# Shield_schematic.net
KiCad netlist of a schematic drawn in EAGLE
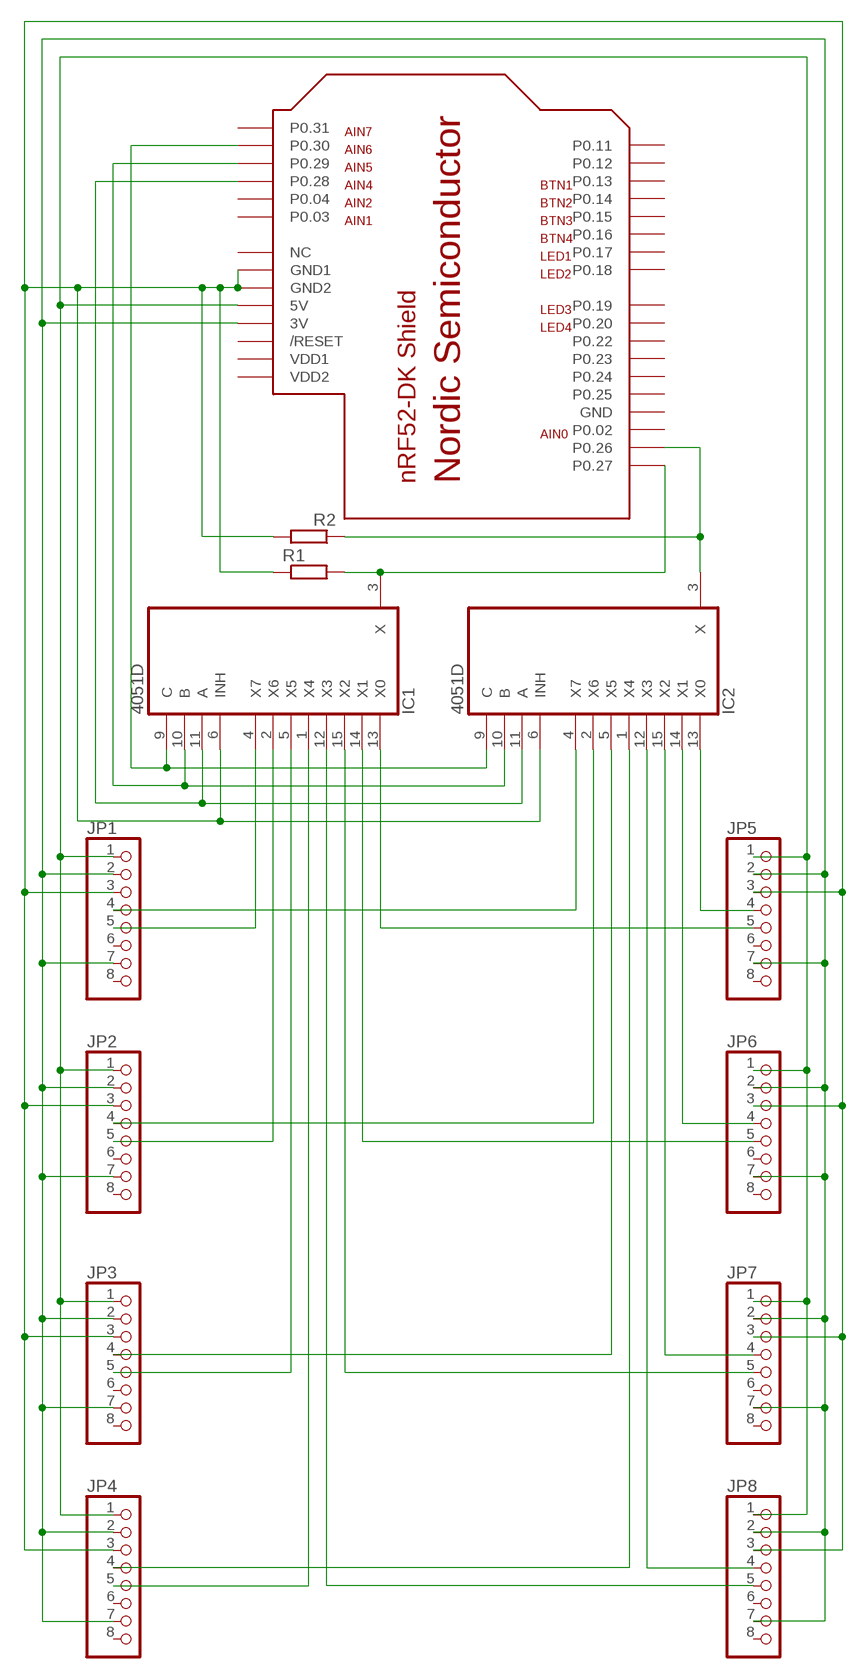
[diagram p0: schematic, sheet 1]

(export (version "E")
  (design (tool "Eeschema 10.0.6"))
  (components
    (comp (ref "IC1")
      (value "4051D")
      (footprint "eagle-import:SO16")
      (libsource (lib "eagle-import") (part "4051D"))
    )
    (comp (ref "IC2")
      (value "4051D")
      (footprint "eagle-import:SO16")
      (libsource (lib "eagle-import") (part "4051D"))
    )
    (comp (ref "JP1")
      (value "PINHD-1X8")
      (footprint "eagle-import:1X08")
      (libsource (lib "eagle-import") (part "PINHD-1X8"))
    )
    (comp (ref "JP2")
      (value "PINHD-1X8")
      (footprint "eagle-import:1X08")
      (libsource (lib "eagle-import") (part "PINHD-1X8"))
    )
    (comp (ref "JP3")
      (value "PINHD-1X8")
      (footprint "eagle-import:1X08")
      (libsource (lib "eagle-import") (part "PINHD-1X8"))
    )
    (comp (ref "JP4")
      (value "PINHD-1X8")
      (footprint "eagle-import:1X08")
      (libsource (lib "eagle-import") (part "PINHD-1X8"))
    )
    (comp (ref "JP5")
      (value "PINHD-1X8")
      (footprint "eagle-import:1X08")
      (libsource (lib "eagle-import") (part "PINHD-1X8"))
    )
    (comp (ref "JP6")
      (value "PINHD-1X8")
      (footprint "eagle-import:1X08")
      (libsource (lib "eagle-import") (part "PINHD-1X8"))
    )
    (comp (ref "JP7")
      (value "PINHD-1X8")
      (footprint "eagle-import:1X08")
      (libsource (lib "eagle-import") (part "PINHD-1X8"))
    )
    (comp (ref "JP8")
      (value "PINHD-1X8")
      (footprint "eagle-import:1X08")
      (libsource (lib "eagle-import") (part "PINHD-1X8"))
    )
    (comp (ref "R1")
      (value "R-EU_0411/15")
      (footprint "eagle-import:0411_15")
      (libsource (lib "eagle-import") (part "R-EU_0411/15"))
    )
    (comp (ref "R2")
      (value "R-EU_0411/15")
      (footprint "eagle-import:0411_15")
      (libsource (lib "eagle-import") (part "R-EU_0411/15"))
    )
    (comp (ref "U$1")
      (value "NRF52-SHIELD-NOTEXT")
      (footprint "eagle-import:NRF52-SHIELD")
      (libsource (lib "eagle-import") (part "NRF52-SHIELD-NOTEXT"))
    )
  )
  (nets
    (net (code "1") (name "/GND") (class "Default")
      (node (ref "U$1") (pin "GND") (pinfunction "GND_GND") (pintype "power_in"))
    )
    (net (code "2") (name "/VDD1") (class "Default")
      (node (ref "U$1") (pin "VDD2") (pinfunction "VDD1_VDD2") (pintype "power_in"))
    )
    (net (code "3") (name "/VDD2") (class "Default")
      (node (ref "U$1") (pin "VDD1") (pinfunction "VDD2_VDD1") (pintype "power_in"))
    )
    (net (code "4") (name "Net-(IC1A-A)") (class "Default")
      (node (ref "IC1") (pin "11") (pinfunction "A_11") (pintype "input"))
      (node (ref "IC2") (pin "11") (pinfunction "A_11") (pintype "input"))
      (node (ref "U$1") (pin "P28") (pinfunction "P0.28_P28") (pintype "bidirectional"))
    )
    (net (code "5") (name "Net-(IC1A-B)") (class "Default")
      (node (ref "IC1") (pin "10") (pinfunction "B_10") (pintype "input"))
      (node (ref "IC2") (pin "10") (pinfunction "B_10") (pintype "input"))
      (node (ref "U$1") (pin "P29") (pinfunction "P0.29_P29") (pintype "bidirectional"))
    )
    (net (code "6") (name "Net-(IC1A-C)") (class "Default")
      (node (ref "IC1") (pin "9") (pinfunction "C_9") (pintype "input"))
      (node (ref "IC2") (pin "9") (pinfunction "C_9") (pintype "input"))
      (node (ref "U$1") (pin "P30") (pinfunction "P0.30_P30") (pintype "bidirectional"))
    )
    (net (code "7") (name "Net-(IC1A-INH)") (class "Default")
      (node (ref "IC1") (pin "6") (pinfunction "INH_6") (pintype "input"))
      (node (ref "IC2") (pin "6") (pinfunction "INH_6") (pintype "input"))
      (node (ref "JP1") (pin "3") (pinfunction "3_3") (pintype "passive"))
      (node (ref "JP2") (pin "3") (pinfunction "3_3") (pintype "passive"))
      (node (ref "JP3") (pin "3") (pinfunction "3_3") (pintype "passive"))
      (node (ref "JP4") (pin "3") (pinfunction "3_3") (pintype "passive"))
      (node (ref "JP5") (pin "3") (pinfunction "3_3") (pintype "passive"))
      (node (ref "JP6") (pin "3") (pinfunction "3_3") (pintype "passive"))
      (node (ref "JP7") (pin "3") (pinfunction "3_3") (pintype "passive"))
      (node (ref "JP8") (pin "3") (pinfunction "3_3") (pintype "passive"))
      (node (ref "R1") (pin "1") (pinfunction "1_1") (pintype "passive"))
      (node (ref "R2") (pin "2") (pinfunction "2_2") (pintype "passive"))
      (node (ref "U$1") (pin "GND1") (pinfunction "GND1_GND1") (pintype "power_in"))
      (node (ref "U$1") (pin "GND2") (pinfunction "GND2_GND2") (pintype "power_in"))
    )
    (net (code "8") (name "Net-(IC1A-X)") (class "Default")
      (node (ref "IC1") (pin "3") (pinfunction "X_3") (pintype "bidirectional"))
      (node (ref "R1") (pin "2") (pinfunction "2_2") (pintype "passive"))
      (node (ref "U$1") (pin "P27") (pinfunction "P0.27_P27") (pintype "bidirectional"))
    )
    (net (code "9") (name "Net-(IC1A-X0)") (class "Default")
      (node (ref "IC1") (pin "13") (pinfunction "X0_13") (pintype "bidirectional"))
      (node (ref "JP5") (pin "5") (pinfunction "5_5") (pintype "passive"))
    )
    (net (code "10") (name "Net-(IC1A-X1)") (class "Default")
      (node (ref "IC1") (pin "14") (pinfunction "X1_14") (pintype "bidirectional"))
      (node (ref "JP6") (pin "5") (pinfunction "5_5") (pintype "passive"))
    )
    (net (code "11") (name "Net-(IC1A-X2)") (class "Default")
      (node (ref "IC1") (pin "15") (pinfunction "X2_15") (pintype "bidirectional"))
      (node (ref "JP7") (pin "5") (pinfunction "5_5") (pintype "passive"))
    )
    (net (code "12") (name "Net-(IC1A-X3)") (class "Default")
      (node (ref "IC1") (pin "12") (pinfunction "X3_12") (pintype "bidirectional"))
      (node (ref "JP8") (pin "5") (pinfunction "5_5") (pintype "passive"))
    )
    (net (code "13") (name "Net-(IC1A-X4)") (class "Default")
      (node (ref "IC1") (pin "1") (pinfunction "X4_1") (pintype "bidirectional"))
      (node (ref "JP4") (pin "5") (pinfunction "5_5") (pintype "passive"))
    )
    (net (code "14") (name "Net-(IC1A-X5)") (class "Default")
      (node (ref "IC1") (pin "5") (pinfunction "X5_5") (pintype "bidirectional"))
      (node (ref "JP3") (pin "5") (pinfunction "5_5") (pintype "passive"))
    )
    (net (code "15") (name "Net-(IC1A-X6)") (class "Default")
      (node (ref "IC1") (pin "2") (pinfunction "X6_2") (pintype "bidirectional"))
      (node (ref "JP2") (pin "5") (pinfunction "5_5") (pintype "passive"))
    )
    (net (code "16") (name "Net-(IC1A-X7)") (class "Default")
      (node (ref "IC1") (pin "4") (pinfunction "X7_4") (pintype "bidirectional"))
      (node (ref "JP1") (pin "5") (pinfunction "5_5") (pintype "passive"))
    )
    (net (code "17") (name "Net-(IC2A-X)") (class "Default")
      (node (ref "IC2") (pin "3") (pinfunction "X_3") (pintype "bidirectional"))
      (node (ref "R2") (pin "1") (pinfunction "1_1") (pintype "passive"))
      (node (ref "U$1") (pin "P26") (pinfunction "P0.26_P26") (pintype "bidirectional"))
    )
    (net (code "18") (name "Net-(IC2A-X0)") (class "Default")
      (node (ref "IC2") (pin "13") (pinfunction "X0_13") (pintype "bidirectional"))
      (node (ref "JP5") (pin "4") (pinfunction "4_4") (pintype "passive"))
    )
    (net (code "19") (name "Net-(IC2A-X1)") (class "Default")
      (node (ref "IC2") (pin "14") (pinfunction "X1_14") (pintype "bidirectional"))
      (node (ref "JP6") (pin "4") (pinfunction "4_4") (pintype "passive"))
    )
    (net (code "20") (name "Net-(IC2A-X2)") (class "Default")
      (node (ref "IC2") (pin "15") (pinfunction "X2_15") (pintype "bidirectional"))
      (node (ref "JP7") (pin "4") (pinfunction "4_4") (pintype "passive"))
    )
    (net (code "21") (name "Net-(IC2A-X3)") (class "Default")
      (node (ref "IC2") (pin "12") (pinfunction "X3_12") (pintype "bidirectional"))
      (node (ref "JP8") (pin "4") (pinfunction "4_4") (pintype "passive"))
    )
    (net (code "22") (name "Net-(IC2A-X4)") (class "Default")
      (node (ref "IC2") (pin "1") (pinfunction "X4_1") (pintype "bidirectional"))
      (node (ref "JP4") (pin "4") (pinfunction "4_4") (pintype "passive"))
    )
    (net (code "23") (name "Net-(IC2A-X5)") (class "Default")
      (node (ref "IC2") (pin "5") (pinfunction "X5_5") (pintype "bidirectional"))
      (node (ref "JP3") (pin "4") (pinfunction "4_4") (pintype "passive"))
    )
    (net (code "24") (name "Net-(IC2A-X6)") (class "Default")
      (node (ref "IC2") (pin "2") (pinfunction "X6_2") (pintype "bidirectional"))
      (node (ref "JP2") (pin "4") (pinfunction "4_4") (pintype "passive"))
    )
    (net (code "25") (name "Net-(IC2A-X7)") (class "Default")
      (node (ref "IC2") (pin "4") (pinfunction "X7_4") (pintype "bidirectional"))
      (node (ref "JP1") (pin "4") (pinfunction "4_4") (pintype "passive"))
    )
    (net (code "26") (name "Net-(JP1-Pad1)") (class "Default")
      (node (ref "JP1") (pin "1") (pinfunction "1_1") (pintype "passive"))
      (node (ref "JP2") (pin "1") (pinfunction "1_1") (pintype "passive"))
      (node (ref "JP3") (pin "1") (pinfunction "1_1") (pintype "passive"))
      (node (ref "JP4") (pin "1") (pinfunction "1_1") (pintype "passive"))
      (node (ref "JP5") (pin "1") (pinfunction "1_1") (pintype "passive"))
      (node (ref "JP6") (pin "1") (pinfunction "1_1") (pintype "passive"))
      (node (ref "JP7") (pin "1") (pinfunction "1_1") (pintype "passive"))
      (node (ref "JP8") (pin "1") (pinfunction "1_1") (pintype "passive"))
      (node (ref "U$1") (pin "5V") (pinfunction "5V_5V") (pintype "power_in"))
    )
    (net (code "27") (name "Net-(JP1-Pad2)") (class "Default")
      (node (ref "JP1") (pin "2") (pinfunction "2_2") (pintype "passive"))
      (node (ref "JP1") (pin "7") (pinfunction "7_7") (pintype "passive"))
      (node (ref "JP2") (pin "2") (pinfunction "2_2") (pintype "passive"))
      (node (ref "JP2") (pin "7") (pinfunction "7_7") (pintype "passive"))
      (node (ref "JP3") (pin "2") (pinfunction "2_2") (pintype "passive"))
      (node (ref "JP3") (pin "7") (pinfunction "7_7") (pintype "passive"))
      (node (ref "JP4") (pin "2") (pinfunction "2_2") (pintype "passive"))
      (node (ref "JP4") (pin "7") (pinfunction "7_7") (pintype "passive"))
      (node (ref "JP5") (pin "2") (pinfunction "2_2") (pintype "passive"))
      (node (ref "JP5") (pin "7") (pinfunction "7_7") (pintype "passive"))
      (node (ref "JP6") (pin "2") (pinfunction "2_2") (pintype "passive"))
      (node (ref "JP6") (pin "7") (pinfunction "7_7") (pintype "passive"))
      (node (ref "JP7") (pin "2") (pinfunction "2_2") (pintype "passive"))
      (node (ref "JP7") (pin "7") (pinfunction "7_7") (pintype "passive"))
      (node (ref "JP8") (pin "2") (pinfunction "2_2") (pintype "passive"))
      (node (ref "JP8") (pin "7") (pinfunction "7_7") (pintype "passive"))
      (node (ref "U$1") (pin "3V") (pinfunction "3V_3V") (pintype "power_in"))
    )
    (net (code "28") (name "unconnected-(JP1-Pad6)") (class "Default")
      (node (ref "JP1") (pin "6") (pinfunction "6_6") (pintype "passive"))
    )
    (net (code "29") (name "unconnected-(JP1-Pad8)") (class "Default")
      (node (ref "JP1") (pin "8") (pinfunction "8_8") (pintype "passive"))
    )
    (net (code "30") (name "unconnected-(JP2-Pad6)") (class "Default")
      (node (ref "JP2") (pin "6") (pinfunction "6_6") (pintype "passive"))
    )
    (net (code "31") (name "unconnected-(JP2-Pad8)") (class "Default")
      (node (ref "JP2") (pin "8") (pinfunction "8_8") (pintype "passive"))
    )
    (net (code "32") (name "unconnected-(JP3-Pad6)") (class "Default")
      (node (ref "JP3") (pin "6") (pinfunction "6_6") (pintype "passive"))
    )
    (net (code "33") (name "unconnected-(JP3-Pad8)") (class "Default")
      (node (ref "JP3") (pin "8") (pinfunction "8_8") (pintype "passive"))
    )
    (net (code "34") (name "unconnected-(JP4-Pad6)") (class "Default")
      (node (ref "JP4") (pin "6") (pinfunction "6_6") (pintype "passive"))
    )
    (net (code "35") (name "unconnected-(JP4-Pad8)") (class "Default")
      (node (ref "JP4") (pin "8") (pinfunction "8_8") (pintype "passive"))
    )
    (net (code "36") (name "unconnected-(JP5-Pad6)") (class "Default")
      (node (ref "JP5") (pin "6") (pinfunction "6_6") (pintype "passive"))
    )
    (net (code "37") (name "unconnected-(JP5-Pad8)") (class "Default")
      (node (ref "JP5") (pin "8") (pinfunction "8_8") (pintype "passive"))
    )
    (net (code "38") (name "unconnected-(JP6-Pad6)") (class "Default")
      (node (ref "JP6") (pin "6") (pinfunction "6_6") (pintype "passive"))
    )
    (net (code "39") (name "unconnected-(JP6-Pad8)") (class "Default")
      (node (ref "JP6") (pin "8") (pinfunction "8_8") (pintype "passive"))
    )
    (net (code "40") (name "unconnected-(JP7-Pad6)") (class "Default")
      (node (ref "JP7") (pin "6") (pinfunction "6_6") (pintype "passive"))
    )
    (net (code "41") (name "unconnected-(JP7-Pad8)") (class "Default")
      (node (ref "JP7") (pin "8") (pinfunction "8_8") (pintype "passive"))
    )
    (net (code "42") (name "unconnected-(JP8-Pad6)") (class "Default")
      (node (ref "JP8") (pin "6") (pinfunction "6_6") (pintype "passive"))
    )
    (net (code "43") (name "unconnected-(JP8-Pad8)") (class "Default")
      (node (ref "JP8") (pin "8") (pinfunction "8_8") (pintype "passive"))
    )
    (net (code "44") (name "unconnected-(U$1-P0.02-PadP02)") (class "Default")
      (node (ref "U$1") (pin "P02") (pinfunction "P0.02_P02") (pintype "bidirectional"))
    )
    (net (code "45") (name "unconnected-(U$1-P0.03-PadP03)") (class "Default")
      (node (ref "U$1") (pin "P03") (pinfunction "P0.03_P03") (pintype "bidirectional"))
    )
    (net (code "46") (name "unconnected-(U$1-P0.04-PadP04)") (class "Default")
      (node (ref "U$1") (pin "P04") (pinfunction "P0.04_P04") (pintype "bidirectional"))
    )
    (net (code "47") (name "unconnected-(U$1-P0.11-PadP11)") (class "Default")
      (node (ref "U$1") (pin "P11") (pinfunction "P0.11_P11") (pintype "bidirectional"))
    )
    (net (code "48") (name "unconnected-(U$1-P0.12-PadP12)") (class "Default")
      (node (ref "U$1") (pin "P12") (pinfunction "P0.12_P12") (pintype "bidirectional"))
    )
    (net (code "49") (name "unconnected-(U$1-P0.13-PadP13)") (class "Default")
      (node (ref "U$1") (pin "P13") (pinfunction "P0.13_P13") (pintype "bidirectional"))
    )
    (net (code "50") (name "unconnected-(U$1-P0.14-PadP14)") (class "Default")
      (node (ref "U$1") (pin "P14") (pinfunction "P0.14_P14") (pintype "bidirectional"))
    )
    (net (code "51") (name "unconnected-(U$1-P0.15-PadP15)") (class "Default")
      (node (ref "U$1") (pin "P15") (pinfunction "P0.15_P15") (pintype "bidirectional"))
    )
    (net (code "52") (name "unconnected-(U$1-P0.16-PadP16)") (class "Default")
      (node (ref "U$1") (pin "P16") (pinfunction "P0.16_P16") (pintype "bidirectional"))
    )
    (net (code "53") (name "unconnected-(U$1-P0.17-PadP17)") (class "Default")
      (node (ref "U$1") (pin "P17") (pinfunction "P0.17_P17") (pintype "bidirectional"))
    )
    (net (code "54") (name "unconnected-(U$1-P0.18-PadP18)") (class "Default")
      (node (ref "U$1") (pin "P18") (pinfunction "P0.18_P18") (pintype "bidirectional"))
    )
    (net (code "55") (name "unconnected-(U$1-P0.19-PadP19)") (class "Default")
      (node (ref "U$1") (pin "P19") (pinfunction "P0.19_P19") (pintype "bidirectional"))
    )
    (net (code "56") (name "unconnected-(U$1-P0.20-PadP20)") (class "Default")
      (node (ref "U$1") (pin "P20") (pinfunction "P0.20_P20") (pintype "bidirectional"))
    )
    (net (code "57") (name "unconnected-(U$1-P0.22-PadP22)") (class "Default")
      (node (ref "U$1") (pin "P22") (pinfunction "P0.22_P22") (pintype "bidirectional"))
    )
    (net (code "58") (name "unconnected-(U$1-P0.23-PadP23)") (class "Default")
      (node (ref "U$1") (pin "P23") (pinfunction "P0.23_P23") (pintype "bidirectional"))
    )
    (net (code "59") (name "unconnected-(U$1-P0.24-PadP24)") (class "Default")
      (node (ref "U$1") (pin "P24") (pinfunction "P0.24_P24") (pintype "bidirectional"))
    )
    (net (code "60") (name "unconnected-(U$1-P0.25-PadP25)") (class "Default")
      (node (ref "U$1") (pin "P25") (pinfunction "P0.25_P25") (pintype "bidirectional"))
    )
    (net (code "61") (name "unconnected-(U$1-P0.31-PadP31)") (class "Default")
      (node (ref "U$1") (pin "P31") (pinfunction "P0.31_P31") (pintype "bidirectional"))
    )
    (net (code "62") (name "unconnected-(U$1-PadNC)") (class "Default")
      (node (ref "U$1") (pin "NC") (pinfunction "NC_NC") (pintype "no_connect"))
    )
    (net (code "63") (name "unconnected-(U$1-{slash}RESET-PadRESET)") (class "Default")
      (node (ref "U$1") (pin "RESET") (pinfunction "/RESET_RESET") (pintype "bidirectional"))
    )
  )
)
